# Motor_Control.net
KiCad netlist of a schematic drawn in Altium Designer
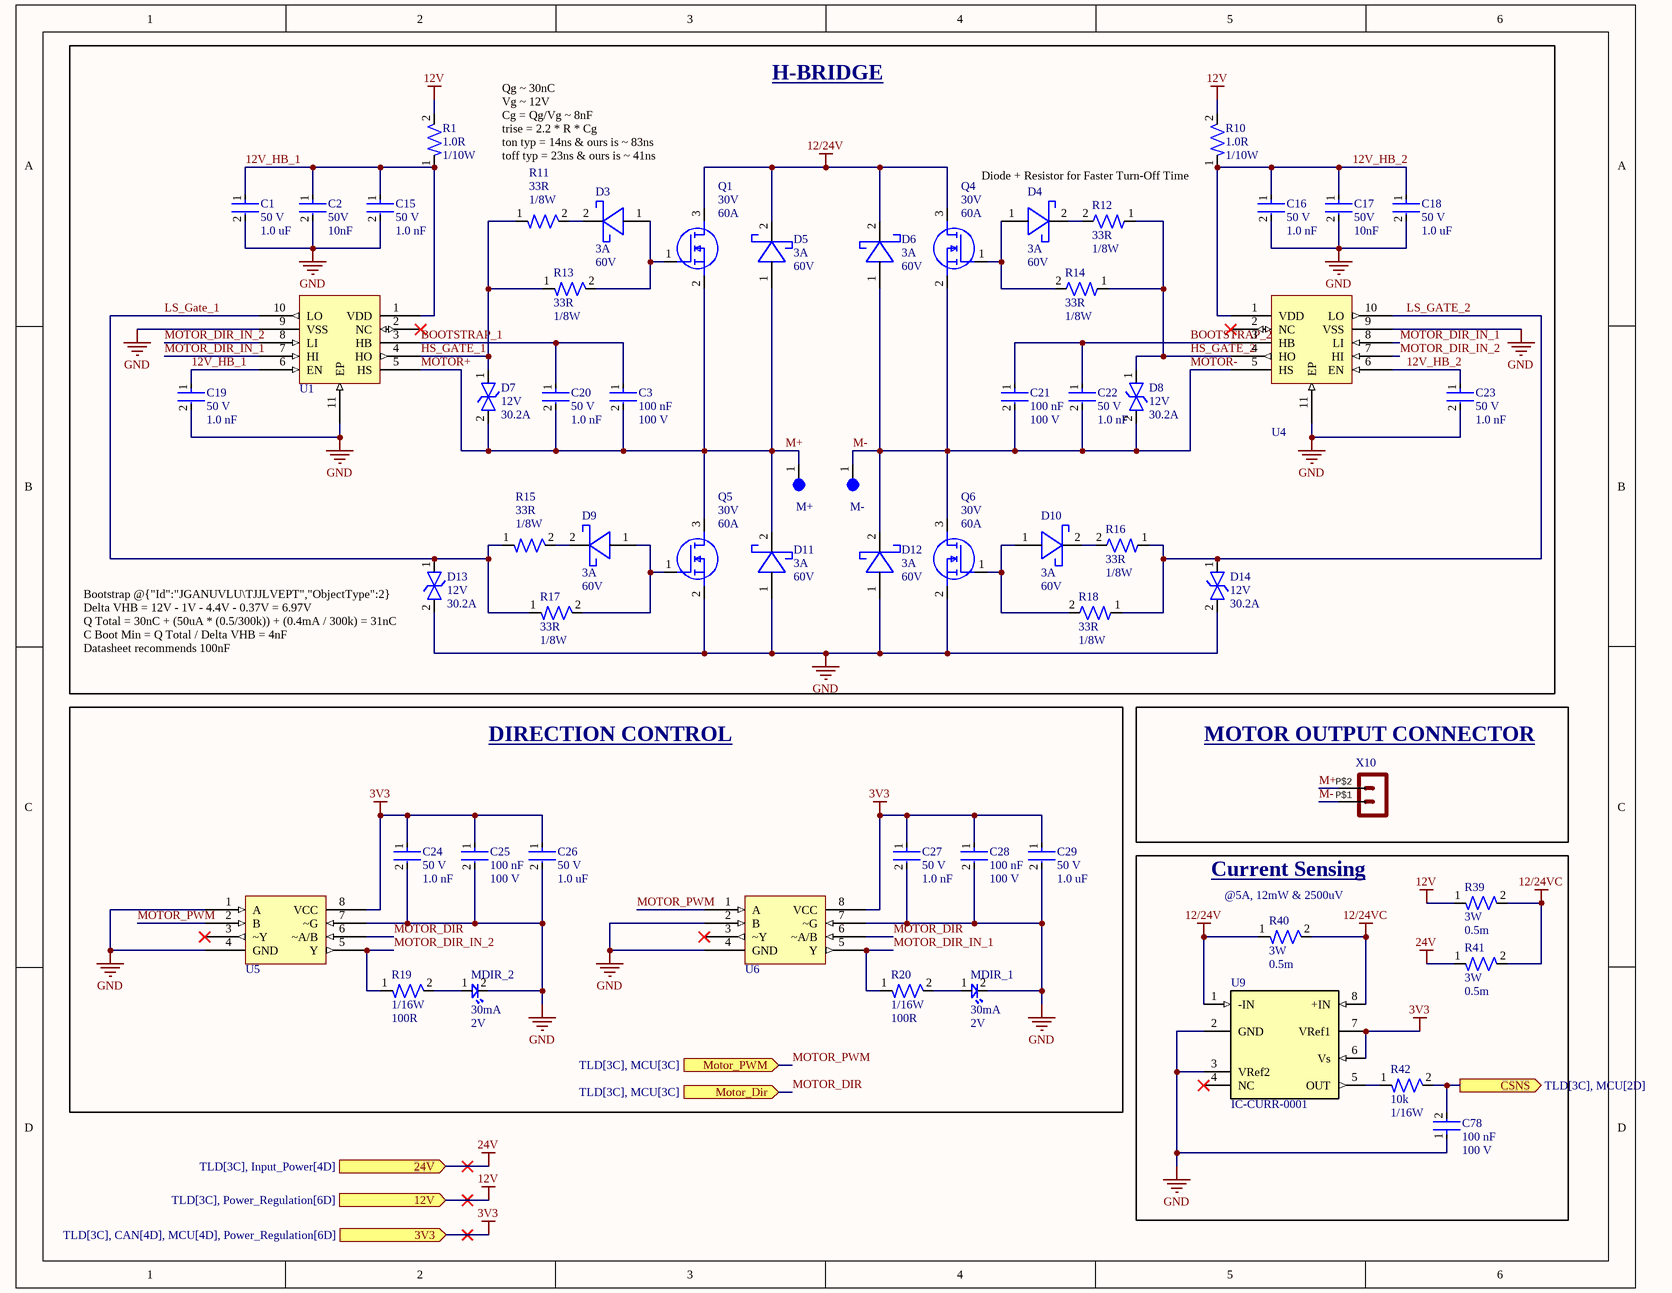
[diagram p0: Motor_Control.SchDoc]

(export (version "E")
  (design (tool "Eeschema 10.0.6"))
  (components
    (comp (ref "C1")
      (value "CC0805KKX7R9BB105")
      (footprint "CAP-0805")
      (description "CAP CER 1UF 50V X7R 0805")
      (fields (field (name "VOLTAGE") "50 V") (field (name "CAPACITANCE") "1.0 uF"))
      (libsource (lib "JLC_25") (part "CAP-1U-0001"))
    )
    (comp (ref "C2")
      (value "GRM2195C1H103JA01D")
      (footprint "CAP-0805")
      (description "CAP CER 10000PF 50V C0G/NP0 0805")
      (fields (field (name "VOLTAGE") "50V") (field (name "CAPACITANCE") "10nF"))
      (libsource (lib "JLC_25") (part "CAP-10N-0001"))
    )
    (comp (ref "C3")
      (value "CC0603KRX7R0BB104")
      (footprint "CAP-0603")
      (description "CAP CER 0.1UF 100V X7R 0603")
      (fields (field (name "CAPACITANCE") "100 nF") (field (name "VOLTAGE") "100 V"))
      (libsource (lib "JLC_25") (part "CAP-100N-0001"))
    )
    (comp (ref "C15")
      (value "CC0402KRX7R9BB102")
      (footprint "CAP-0402")
      (description "CAP CER 1000PF 50V X7R 0402")
      (fields (field (name "VOLTAGE") "50 V") (field (name "CAPACITANCE") "1.0 nF"))
      (libsource (lib "JLC_25") (part "CAP-1N-0001"))
    )
    (comp (ref "C16")
      (value "CC0402KRX7R9BB102")
      (footprint "CAP-0402")
      (description "CAP CER 1000PF 50V X7R 0402")
      (fields (field (name "VOLTAGE") "50 V") (field (name "CAPACITANCE") "1.0 nF"))
      (libsource (lib "JLC_25") (part "CAP-1N-0001"))
    )
    (comp (ref "C17")
      (value "GRM2195C1H103JA01D")
      (footprint "CAP-0805")
      (description "CAP CER 10000PF 50V C0G/NP0 0805")
      (fields (field (name "VOLTAGE") "50V") (field (name "CAPACITANCE") "10nF"))
      (libsource (lib "JLC_25") (part "CAP-10N-0001"))
    )
    (comp (ref "C18")
      (value "CC0805KKX7R9BB105")
      (footprint "CAP-0805")
      (description "CAP CER 1UF 50V X7R 0805")
      (fields (field (name "VOLTAGE") "50 V") (field (name "CAPACITANCE") "1.0 uF"))
      (libsource (lib "JLC_25") (part "CAP-1U-0001"))
    )
    (comp (ref "C19")
      (value "CC0402KRX7R9BB102")
      (footprint "CAP-0402")
      (description "CAP CER 1000PF 50V X7R 0402")
      (fields (field (name "VOLTAGE") "50 V") (field (name "CAPACITANCE") "1.0 nF"))
      (libsource (lib "JLC_25") (part "CAP-1N-0001"))
    )
    (comp (ref "C20")
      (value "CC0402KRX7R9BB102")
      (footprint "CAP-0402")
      (description "CAP CER 1000PF 50V X7R 0402")
      (fields (field (name "VOLTAGE") "50 V") (field (name "CAPACITANCE") "1.0 nF"))
      (libsource (lib "JLC_25") (part "CAP-1N-0001"))
    )
    (comp (ref "C21")
      (value "CC0603KRX7R0BB104")
      (footprint "CAP-0603")
      (description "CAP CER 0.1UF 100V X7R 0603")
      (fields (field (name "CAPACITANCE") "100 nF") (field (name "VOLTAGE") "100 V"))
      (libsource (lib "JLC_25") (part "CAP-100N-0001"))
    )
    (comp (ref "C22")
      (value "CC0402KRX7R9BB102")
      (footprint "CAP-0402")
      (description "CAP CER 1000PF 50V X7R 0402")
      (fields (field (name "VOLTAGE") "50 V") (field (name "CAPACITANCE") "1.0 nF"))
      (libsource (lib "JLC_25") (part "CAP-1N-0001"))
    )
    (comp (ref "C23")
      (value "CC0402KRX7R9BB102")
      (footprint "CAP-0402")
      (description "CAP CER 1000PF 50V X7R 0402")
      (fields (field (name "VOLTAGE") "50 V") (field (name "CAPACITANCE") "1.0 nF"))
      (libsource (lib "JLC_25") (part "CAP-1N-0001"))
    )
    (comp (ref "C24")
      (value "CC0402KRX7R9BB102")
      (footprint "CAP-0402")
      (description "CAP CER 1000PF 50V X7R 0402")
      (fields (field (name "VOLTAGE") "50 V") (field (name "CAPACITANCE") "1.0 nF"))
      (libsource (lib "JLC_25") (part "CAP-1N-0001"))
    )
    (comp (ref "C25")
      (value "CC0603KRX7R0BB104")
      (footprint "CAP-0603")
      (description "CAP CER 0.1UF 100V X7R 0603")
      (fields (field (name "CAPACITANCE") "100 nF") (field (name "VOLTAGE") "100 V"))
      (libsource (lib "JLC_25") (part "CAP-100N-0001"))
    )
    (comp (ref "C26")
      (value "CC0805KKX7R9BB105")
      (footprint "CAP-0805")
      (description "CAP CER 1UF 50V X7R 0805")
      (fields (field (name "VOLTAGE") "50 V") (field (name "CAPACITANCE") "1.0 uF"))
      (libsource (lib "JLC_25") (part "CAP-1U-0001"))
    )
    (comp (ref "C27")
      (value "CC0402KRX7R9BB102")
      (footprint "CAP-0402")
      (description "CAP CER 1000PF 50V X7R 0402")
      (fields (field (name "VOLTAGE") "50 V") (field (name "CAPACITANCE") "1.0 nF"))
      (libsource (lib "JLC_25") (part "CAP-1N-0001"))
    )
    (comp (ref "C28")
      (value "CC0603KRX7R0BB104")
      (footprint "CAP-0603")
      (description "CAP CER 0.1UF 100V X7R 0603")
      (fields (field (name "CAPACITANCE") "100 nF") (field (name "VOLTAGE") "100 V"))
      (libsource (lib "JLC_25") (part "CAP-100N-0001"))
    )
    (comp (ref "C29")
      (value "CC0805KKX7R9BB105")
      (footprint "CAP-0805")
      (description "CAP CER 1UF 50V X7R 0805")
      (fields (field (name "VOLTAGE") "50 V") (field (name "CAPACITANCE") "1.0 uF"))
      (libsource (lib "JLC_25") (part "CAP-1U-0001"))
    )
    (comp (ref "C78")
      (value "CC0603KRX7R0BB104")
      (footprint "CAP-0603")
      (description "CAP CER 0.1UF 100V X7R 0603")
      (fields (field (name "CAPACITANCE") "100 nF") (field (name "VOLTAGE") "100 V"))
      (libsource (lib "JLC_25") (part "CAP-100N-0001"))
    )
    (comp (ref "D3")
      (value "PMEG6030EP,115")
      (footprint "DIO-SOD128")
      (description "DIODE SCHOTTKY 60V 3A SOD128")
      (fields (field (name "CURRENT RATING") "3A") (field (name "REVERSE VOLTAGE") "60V"))
      (libsource (lib "JLC_25") (part "DIO-SCHOTTKY-0003"))
    )
    (comp (ref "D4")
      (value "PMEG6030EP,115")
      (footprint "DIO-SOD128")
      (description "DIODE SCHOTTKY 60V 3A SOD128")
      (fields (field (name "CURRENT RATING") "3A") (field (name "REVERSE VOLTAGE") "60V"))
      (libsource (lib "JLC_25") (part "DIO-SCHOTTKY-0003"))
    )
    (comp (ref "D5")
      (value "PMEG6030EP,115")
      (footprint "DIO-SOD128")
      (description "DIODE SCHOTTKY 60V 3A SOD128")
      (fields (field (name "CURRENT RATING") "3A") (field (name "REVERSE VOLTAGE") "60V"))
      (libsource (lib "JLC_25") (part "DIO-SCHOTTKY-0003"))
    )
    (comp (ref "D6")
      (value "PMEG6030EP,115")
      (footprint "DIO-SOD128")
      (description "DIODE SCHOTTKY 60V 3A SOD128")
      (fields (field (name "CURRENT RATING") "3A") (field (name "REVERSE VOLTAGE") "60V"))
      (libsource (lib "JLC_25") (part "DIO-SCHOTTKY-0003"))
    )
    (comp (ref "D7")
      (value "SMBJ12CA")
      (footprint "DO-214AA (SMBJ)")
      (description "TVS DIODE 12VWM 19.9VC DO214AA")
      (fields (field (name "STANDOFF VOLTAGE") "12V") (field (name "CURRENT RATING") "30.2A"))
      (libsource (lib "JLC_25") (part "DIO-TVS-0002"))
    )
    (comp (ref "D8")
      (value "SMBJ12CA")
      (footprint "DO-214AA (SMBJ)")
      (description "TVS DIODE 12VWM 19.9VC DO214AA")
      (fields (field (name "STANDOFF VOLTAGE") "12V") (field (name "CURRENT RATING") "30.2A"))
      (libsource (lib "JLC_25") (part "DIO-TVS-0002"))
    )
    (comp (ref "D9")
      (value "PMEG6030EP,115")
      (footprint "DIO-SOD128")
      (description "DIODE SCHOTTKY 60V 3A SOD128")
      (fields (field (name "CURRENT RATING") "3A") (field (name "REVERSE VOLTAGE") "60V"))
      (libsource (lib "JLC_25") (part "DIO-SCHOTTKY-0003"))
    )
    (comp (ref "D10")
      (value "PMEG6030EP,115")
      (footprint "DIO-SOD128")
      (description "DIODE SCHOTTKY 60V 3A SOD128")
      (fields (field (name "CURRENT RATING") "3A") (field (name "REVERSE VOLTAGE") "60V"))
      (libsource (lib "JLC_25") (part "DIO-SCHOTTKY-0003"))
    )
    (comp (ref "D11")
      (value "PMEG6030EP,115")
      (footprint "DIO-SOD128")
      (description "DIODE SCHOTTKY 60V 3A SOD128")
      (fields (field (name "CURRENT RATING") "3A") (field (name "REVERSE VOLTAGE") "60V"))
      (libsource (lib "JLC_25") (part "DIO-SCHOTTKY-0003"))
    )
    (comp (ref "D12")
      (value "PMEG6030EP,115")
      (footprint "DIO-SOD128")
      (description "DIODE SCHOTTKY 60V 3A SOD128")
      (fields (field (name "CURRENT RATING") "3A") (field (name "REVERSE VOLTAGE") "60V"))
      (libsource (lib "JLC_25") (part "DIO-SCHOTTKY-0003"))
    )
    (comp (ref "D13")
      (value "SMBJ12CA")
      (footprint "DO-214AA (SMBJ)")
      (description "TVS DIODE 12VWM 19.9VC DO214AA")
      (fields (field (name "STANDOFF VOLTAGE") "12V") (field (name "CURRENT RATING") "30.2A"))
      (libsource (lib "JLC_25") (part "DIO-TVS-0002"))
    )
    (comp (ref "D14")
      (value "SMBJ12CA")
      (footprint "DO-214AA (SMBJ)")
      (description "TVS DIODE 12VWM 19.9VC DO214AA")
      (fields (field (name "STANDOFF VOLTAGE") "12V") (field (name "CURRENT RATING") "30.2A"))
      (libsource (lib "JLC_25") (part "DIO-TVS-0002"))
    )
    (comp (ref "M+")
      (value "5003")
      (footprint "TEST-POINT-0001")
      (description "Oranange PC Test Point, Miniature Phoisphor Bronze Silver Plating Through Hole Mounting Type")
      (libsource (lib "JLC_25") (part "TEST-POINT-0001"))
    )
    (comp (ref "M-")
      (value "5003")
      (footprint "TEST-POINT-0001")
      (description "Oranange PC Test Point, Miniature Phoisphor Bronze Silver Plating Through Hole Mounting Type")
      (libsource (lib "JLC_25") (part "TEST-POINT-0001"))
    )
    (comp (ref "MDIR_1")
      (value "BL-HKC36G-AV-TRB")
      (footprint "LED-0603")
      (description "LED YELLOW CLEAR 0603 SMD")
      (fields (field (name "FORWARD CURRENT") "30mA") (field (name "FORWARD VOLTAGE") "2V"))
      (libsource (lib "JLC_25") (part "LED-0001"))
    )
    (comp (ref "MDIR_2")
      (value "BL-HKC36G-AV-TRB")
      (footprint "LED-0603")
      (description "LED YELLOW CLEAR 0603 SMD")
      (fields (field (name "FORWARD CURRENT") "30mA") (field (name "FORWARD VOLTAGE") "2V"))
      (libsource (lib "JLC_25") (part "LED-0001"))
    )
    (comp (ref "Q1")
      (value "CSD17575Q3")
      (footprint "IC-8VSONCLIP")
      (description "MOSFET N-CH 30V 60A 8VSON")
      (fields (field (name "VOLTAGE") "30V") (field (name "CONTINUOUS CURRENT") "60A"))
      (libsource (lib "JLC_25") (part "NMOS-26A-0001"))
    )
    (comp (ref "Q4")
      (value "CSD17575Q3")
      (footprint "IC-8VSONCLIP")
      (description "MOSFET N-CH 30V 60A 8VSON")
      (fields (field (name "VOLTAGE") "30V") (field (name "CONTINUOUS CURRENT") "60A"))
      (libsource (lib "JLC_25") (part "NMOS-26A-0001"))
    )
    (comp (ref "Q5")
      (value "CSD17575Q3")
      (footprint "IC-8VSONCLIP")
      (description "MOSFET N-CH 30V 60A 8VSON")
      (fields (field (name "VOLTAGE") "30V") (field (name "CONTINUOUS CURRENT") "60A"))
      (libsource (lib "JLC_25") (part "NMOS-26A-0001"))
    )
    (comp (ref "Q6")
      (value "CSD17575Q3")
      (footprint "IC-8VSONCLIP")
      (description "MOSFET N-CH 30V 60A 8VSON")
      (fields (field (name "VOLTAGE") "30V") (field (name "CONTINUOUS CURRENT") "60A"))
      (libsource (lib "JLC_25") (part "NMOS-26A-0001"))
    )
    (comp (ref "R1")
      (value "ERJ2GEJ1R0X")
      (footprint "RES-0402")
      (description "RES SMD 1 OHM 5% 1/10W 0402")
      (fields
        (field (name "TOLERANCE") "5%")
        (field (name "RESISTANCE") "1.0R")
        (field (name "POWER") "1/10W")
      )
      (libsource (lib "JLC_25") (part "RES-1-0001"))
    )
    (comp (ref "R10")
      (value "ERJ2GEJ1R0X")
      (footprint "RES-0402")
      (description "RES SMD 1 OHM 5% 1/10W 0402")
      (fields
        (field (name "TOLERANCE") "5%")
        (field (name "RESISTANCE") "1.0R")
        (field (name "POWER") "1/10W")
      )
      (libsource (lib "JLC_25") (part "RES-1-0001"))
    )
    (comp (ref "R11")
      (value "RC0402FR-7W33RL")
      (footprint "RES-0402")
      (description "RES 33 OHM 1% 1/8W 0402")
      (fields (field (name "TOLERANCE") "1%") (field (name "RESISTANCE") "33R") (field (name "POWER") "1/8W"))
      (libsource (lib "JLC_25") (part "RES-33-0001"))
    )
    (comp (ref "R12")
      (value "RC0402FR-7W33RL")
      (footprint "RES-0402")
      (description "RES 33 OHM 1% 1/8W 0402")
      (fields (field (name "TOLERANCE") "1%") (field (name "RESISTANCE") "33R") (field (name "POWER") "1/8W"))
      (libsource (lib "JLC_25") (part "RES-33-0001"))
    )
    (comp (ref "R13")
      (value "RC0402FR-7W33RL")
      (footprint "RES-0402")
      (description "RES 33 OHM 1% 1/8W 0402")
      (fields (field (name "TOLERANCE") "1%") (field (name "RESISTANCE") "33R") (field (name "POWER") "1/8W"))
      (libsource (lib "JLC_25") (part "RES-33-0001"))
    )
    (comp (ref "R14")
      (value "RC0402FR-7W33RL")
      (footprint "RES-0402")
      (description "RES 33 OHM 1% 1/8W 0402")
      (fields (field (name "TOLERANCE") "1%") (field (name "RESISTANCE") "33R") (field (name "POWER") "1/8W"))
      (libsource (lib "JLC_25") (part "RES-33-0001"))
    )
    (comp (ref "R15")
      (value "RC0402FR-7W33RL")
      (footprint "RES-0402")
      (description "RES 33 OHM 1% 1/8W 0402")
      (fields (field (name "TOLERANCE") "1%") (field (name "RESISTANCE") "33R") (field (name "POWER") "1/8W"))
      (libsource (lib "JLC_25") (part "RES-33-0001"))
    )
    (comp (ref "R16")
      (value "RC0402FR-7W33RL")
      (footprint "RES-0402")
      (description "RES 33 OHM 1% 1/8W 0402")
      (fields (field (name "TOLERANCE") "1%") (field (name "RESISTANCE") "33R") (field (name "POWER") "1/8W"))
      (libsource (lib "JLC_25") (part "RES-33-0001"))
    )
    (comp (ref "R17")
      (value "RC0402FR-7W33RL")
      (footprint "RES-0402")
      (description "RES 33 OHM 1% 1/8W 0402")
      (fields (field (name "TOLERANCE") "1%") (field (name "RESISTANCE") "33R") (field (name "POWER") "1/8W"))
      (libsource (lib "JLC_25") (part "RES-33-0001"))
    )
    (comp (ref "R18")
      (value "RC0402FR-7W33RL")
      (footprint "RES-0402")
      (description "RES 33 OHM 1% 1/8W 0402")
      (fields (field (name "TOLERANCE") "1%") (field (name "RESISTANCE") "33R") (field (name "POWER") "1/8W"))
      (libsource (lib "JLC_25") (part "RES-33-0001"))
    )
    (comp (ref "R19")
      (value "RC0402FR-07100RL")
      (footprint "RES-0402")
      (description "RES 100 OHM 1% 1/16W 0402")
      (fields
        (field (name "TOLERANCE") "1%")
        (field (name "POWER") "1/16W")
        (field (name "RESISTANCE") "100R")
      )
      (libsource (lib "JLC_25") (part "RES-100-0001"))
    )
    (comp (ref "R20")
      (value "RC0402FR-07100RL")
      (footprint "RES-0402")
      (description "RES 100 OHM 1% 1/16W 0402")
      (fields
        (field (name "TOLERANCE") "1%")
        (field (name "POWER") "1/16W")
        (field (name "RESISTANCE") "100R")
      )
      (libsource (lib "JLC_25") (part "RES-100-0001"))
    )
    (comp (ref "R39")
      (value "C337220")
      (footprint "RES-2512")
      (description "2512 Chip Resistor - Surface Mount ROHS")
      (fields (field (name "TOLERANCE") "1%") (field (name "POWER") "3W") (field (name "RESISTANCE") "0.5m"))
      (libsource (lib "JLC_25") (part "RES-0.5m-0001"))
    )
    (comp (ref "R40")
      (value "C337220")
      (footprint "RES-2512")
      (description "2512 Chip Resistor - Surface Mount ROHS")
      (fields (field (name "TOLERANCE") "1%") (field (name "POWER") "3W") (field (name "RESISTANCE") "0.5m"))
      (libsource (lib "JLC_25") (part "RES-0.5m-0001"))
    )
    (comp (ref "R41")
      (value "C337220")
      (footprint "RES-2512")
      (description "2512 Chip Resistor - Surface Mount ROHS")
      (fields (field (name "TOLERANCE") "1%") (field (name "POWER") "3W") (field (name "RESISTANCE") "0.5m"))
      (libsource (lib "JLC_25") (part "RES-0.5m-0001"))
    )
    (comp (ref "R42")
      (value "RC0402FR-0710KL")
      (footprint "RES-0402")
      (description "RES 10K OHM 1% 1/16W 0402")
      (fields
        (field (name "TOLERANCE") "1%")
        (field (name "RESISTANCE") "10k")
        (field (name "POWER") "1/16W")
      )
      (libsource (lib "JLC_25") (part "RES-10k-0001"))
    )
    (comp (ref "U1")
      (value "UCC27282DRCR")
      (footprint "IC-10VSON")
      (description "IC GATE DRVR HALF-BRIDGE 10VSON")
      (libsource (lib "") (part "IC-GTDR-0001_1"))
    )
    (comp (ref "U4")
      (value "UCC27282DRCR")
      (footprint "IC-10VSON")
      (description "IC GATE DRVR HALF-BRIDGE 10VSON")
      (libsource (lib "JLC_25") (part "IC-GTDR-0001"))
    )
    (comp (ref "U5")
      (value "SN74LVC2G157DCUR")
      (footprint "IC-8VSSOP")
      (description "Multiplexer 1 x 2:1 8-VSSOP")
      (libsource (lib "JLC_25") (part "IC-MUX-0001"))
    )
    (comp (ref "U6")
      (value "SN74LVC2G157DCUR")
      (footprint "IC-8VSSOP")
      (description "Multiplexer 1 x 2:1 8-VSSOP")
      (libsource (lib "JLC_25") (part "IC-MUX-0001"))
    )
    (comp (ref "U9")
      (value "IC-CURR-0001")
      (footprint "IC-CURR")
      (description "Current Sense Amplifier 1 Circuit 8-MSOP")
      (libsource (lib "JLC_25") (part "IC-CURR-0001"))
    )
    (comp (ref "X10")
      (value "Molex - Micro-Fit 3.0 Series connector,  3.00mm (0.118\") pitch header, 2 positions.")
      (footprint "43650-0200")
      (libsource (lib "Molex Microfit") (part "HEADER_POS2_?43650-0200"))
    )
  )
  (nets
    (net (code "1") (name "/12V_HB_1") (class "Default")
      (node (ref "C1") (pin "1") (pinfunction "1_1") (pintype "passive"))
      (node (ref "C15") (pin "1") (pinfunction "1_1") (pintype "passive"))
      (node (ref "C19") (pin "1") (pinfunction "1_1") (pintype "passive"))
      (node (ref "C2") (pin "1") (pinfunction "1_1") (pintype "passive"))
      (node (ref "R1") (pin "1") (pinfunction "1_1") (pintype "passive"))
      (node (ref "U1") (pin "1") (pinfunction "VDD_1") (pintype "power_in"))
      (node (ref "U1") (pin "6") (pinfunction "EN_6") (pintype "input"))
    )
    (net (code "2") (name "/12V_HB_2") (class "Default")
      (node (ref "C16") (pin "1") (pinfunction "1_1") (pintype "passive"))
      (node (ref "C17") (pin "1") (pinfunction "1_1") (pintype "passive"))
      (node (ref "C18") (pin "1") (pinfunction "1_1") (pintype "passive"))
      (node (ref "C23") (pin "1") (pinfunction "1_1") (pintype "passive"))
      (node (ref "R10") (pin "1") (pinfunction "1_1") (pintype "passive"))
      (node (ref "U4") (pin "1") (pinfunction "VDD_1") (pintype "power_in"))
      (node (ref "U4") (pin "6") (pinfunction "EN_6") (pintype "input"))
    )
    (net (code "3") (name "/BOOTSTRAP_1") (class "Default")
      (node (ref "C20") (pin "1") (pinfunction "1_1") (pintype "passive"))
      (node (ref "C3") (pin "1") (pinfunction "1_1") (pintype "passive"))
      (node (ref "U1") (pin "3") (pinfunction "HB_3") (pintype "power_in"))
    )
    (net (code "4") (name "/BOOTSTRAP_2") (class "Default")
      (node (ref "C21") (pin "1") (pinfunction "1_1") (pintype "passive"))
      (node (ref "C22") (pin "1") (pinfunction "1_1") (pintype "passive"))
      (node (ref "U4") (pin "3") (pinfunction "HB_3") (pintype "power_in"))
    )
    (net (code "5") (name "/CSNS") (class "Default")
      (node (ref "C78") (pin "2") (pinfunction "2_2") (pintype "passive"))
      (node (ref "R42") (pin "2") (pinfunction "2_2") (pintype "passive"))
    )
    (net (code "6") (name "/HS_GATE_1") (class "Default")
      (node (ref "D7") (pin "1") (pintype "passive"))
      (node (ref "R11") (pin "1") (pinfunction "1_1") (pintype "passive"))
      (node (ref "R13") (pin "1") (pinfunction "1_1") (pintype "passive"))
      (node (ref "U1") (pin "4") (pinfunction "HO_4") (pintype "output"))
    )
    (net (code "7") (name "/HS_GATE_2") (class "Default")
      (node (ref "D8") (pin "1") (pintype "passive"))
      (node (ref "R12") (pin "1") (pinfunction "1_1") (pintype "passive"))
      (node (ref "R14") (pin "1") (pinfunction "1_1") (pintype "passive"))
      (node (ref "U4") (pin "4") (pinfunction "HO_4") (pintype "output"))
    )
    (net (code "8") (name "/LS_GATE_2") (class "Default")
      (node (ref "D14") (pin "1") (pintype "passive"))
      (node (ref "R16") (pin "1") (pinfunction "1_1") (pintype "passive"))
      (node (ref "R18") (pin "1") (pinfunction "1_1") (pintype "passive"))
      (node (ref "U4") (pin "10") (pinfunction "LO_10") (pintype "output"))
    )
    (net (code "9") (name "/LS_Gate_1") (class "Default")
      (node (ref "D13") (pin "1") (pintype "passive"))
      (node (ref "R15") (pin "1") (pinfunction "1_1") (pintype "passive"))
      (node (ref "R17") (pin "1") (pinfunction "1_1") (pintype "passive"))
      (node (ref "U1") (pin "10") (pinfunction "LO_10") (pintype "output"))
    )
    (net (code "10") (name "/M+") (class "Default")
      (node (ref "C20") (pin "2") (pinfunction "2_2") (pintype "passive"))
      (node (ref "C3") (pin "2") (pinfunction "2_2") (pintype "passive"))
      (node (ref "D11") (pin "2") (pinfunction "ANODE_2") (pintype "passive"))
      (node (ref "D5") (pin "1") (pinfunction "CATHODE_1") (pintype "passive"))
      (node (ref "D7") (pin "2") (pintype "passive"))
      (node (ref "M+") (pin "1") (pinfunction "0_1") (pintype "passive"))
      (node (ref "Q1") (pin "2") (pinfunction "S_2") (pintype "passive"))
      (node (ref "Q5") (pin "3") (pinfunction "D_3") (pintype "passive"))
      (node (ref "U1") (pin "5") (pinfunction "HS_5") (pintype "power_in"))
      (node (ref "X10") (pin "P$2") (pinfunction "1_P$2") (pintype "passive"))
    )
    (net (code "11") (name "/M-") (class "Default")
      (node (ref "C21") (pin "2") (pinfunction "2_2") (pintype "passive"))
      (node (ref "C22") (pin "2") (pinfunction "2_2") (pintype "passive"))
      (node (ref "D12") (pin "2") (pinfunction "ANODE_2") (pintype "passive"))
      (node (ref "D6") (pin "1") (pinfunction "CATHODE_1") (pintype "passive"))
      (node (ref "D8") (pin "2") (pintype "passive"))
      (node (ref "M-") (pin "1") (pinfunction "0_1") (pintype "passive"))
      (node (ref "Q4") (pin "2") (pinfunction "S_2") (pintype "passive"))
      (node (ref "Q6") (pin "3") (pinfunction "D_3") (pintype "passive"))
      (node (ref "U4") (pin "5") (pinfunction "HS_5") (pintype "power_in"))
      (node (ref "X10") (pin "P$1") (pinfunction "2_P$1") (pintype "passive"))
    )
    (net (code "12") (name "/MOTOR_DIR") (class "Default")
      (node (ref "U5") (pin "6") (pinfunction "~A/B_6") (pintype "input"))
      (node (ref "U6") (pin "6") (pinfunction "~A/B_6") (pintype "input"))
    )
    (net (code "13") (name "/MOTOR_DIR_IN_1") (class "Default")
      (node (ref "R20") (pin "1") (pinfunction "1_1") (pintype "passive"))
      (node (ref "U1") (pin "7") (pinfunction "HI_7") (pintype "input"))
      (node (ref "U4") (pin "8") (pinfunction "LI_8") (pintype "input"))
      (node (ref "U6") (pin "5") (pinfunction "Y_5") (pintype "output"))
    )
    (net (code "14") (name "/MOTOR_DIR_IN_2") (class "Default")
      (node (ref "R19") (pin "1") (pinfunction "1_1") (pintype "passive"))
      (node (ref "U1") (pin "8") (pinfunction "LI_8") (pintype "input"))
      (node (ref "U4") (pin "7") (pinfunction "HI_7") (pintype "input"))
      (node (ref "U5") (pin "5") (pinfunction "Y_5") (pintype "output"))
    )
    (net (code "15") (name "/MOTOR_PWM") (class "Default")
      (node (ref "U5") (pin "2") (pinfunction "B_2") (pintype "input"))
      (node (ref "U6") (pin "1") (pinfunction "A_1") (pintype "input"))
    )
    (net (code "16") (name "3V3") (class "Default")
      (node (ref "C24") (pin "1") (pinfunction "1_1") (pintype "passive"))
      (node (ref "C25") (pin "1") (pinfunction "1_1") (pintype "passive"))
      (node (ref "C26") (pin "1") (pinfunction "1_1") (pintype "passive"))
      (node (ref "C27") (pin "1") (pinfunction "1_1") (pintype "passive"))
      (node (ref "C28") (pin "1") (pinfunction "1_1") (pintype "passive"))
      (node (ref "C29") (pin "1") (pinfunction "1_1") (pintype "passive"))
      (node (ref "U5") (pin "8") (pinfunction "VCC_8") (pintype "power_in"))
      (node (ref "U6") (pin "8") (pinfunction "VCC_8") (pintype "power_in"))
      (node (ref "U9") (pin "6") (pinfunction "Vs_6") (pintype "input"))
      (node (ref "U9") (pin "7") (pinfunction "VRef1_7") (pintype "power_in"))
    )
    (net (code "17") (name "12V") (class "Default")
      (node (ref "R1") (pin "2") (pinfunction "2_2") (pintype "passive"))
      (node (ref "R10") (pin "2") (pinfunction "2_2") (pintype "passive"))
      (node (ref "R39") (pin "1") (pinfunction "1_1") (pintype "passive"))
    )
    (net (code "18") (name "12{slash}24V") (class "Default")
      (node (ref "D5") (pin "2") (pinfunction "ANODE_2") (pintype "passive"))
      (node (ref "D6") (pin "2") (pinfunction "ANODE_2") (pintype "passive"))
      (node (ref "Q1") (pin "3") (pinfunction "D_3") (pintype "passive"))
      (node (ref "Q4") (pin "3") (pinfunction "D_3") (pintype "passive"))
      (node (ref "R40") (pin "1") (pinfunction "1_1") (pintype "passive"))
      (node (ref "U9") (pin "1") (pinfunction "-IN_1") (pintype "input"))
    )
    (net (code "19") (name "12{slash}24VC") (class "Default")
      (node (ref "R39") (pin "2") (pinfunction "2_2") (pintype "passive"))
      (node (ref "R40") (pin "2") (pinfunction "2_2") (pintype "passive"))
      (node (ref "R41") (pin "2") (pinfunction "2_2") (pintype "passive"))
      (node (ref "U9") (pin "8") (pinfunction "+IN_8") (pintype "input"))
    )
    (net (code "20") (name "24V") (class "Default")
      (node (ref "R41") (pin "1") (pinfunction "1_1") (pintype "passive"))
    )
    (net (code "21") (name "GND") (class "Default")
      (node (ref "C1") (pin "2") (pinfunction "2_2") (pintype "passive"))
      (node (ref "C15") (pin "2") (pinfunction "2_2") (pintype "passive"))
      (node (ref "C16") (pin "2") (pinfunction "2_2") (pintype "passive"))
      (node (ref "C17") (pin "2") (pinfunction "2_2") (pintype "passive"))
      (node (ref "C18") (pin "2") (pinfunction "2_2") (pintype "passive"))
      (node (ref "C19") (pin "2") (pinfunction "2_2") (pintype "passive"))
      (node (ref "C2") (pin "2") (pinfunction "2_2") (pintype "passive"))
      (node (ref "C23") (pin "2") (pinfunction "2_2") (pintype "passive"))
      (node (ref "C24") (pin "2") (pinfunction "2_2") (pintype "passive"))
      (node (ref "C25") (pin "2") (pinfunction "2_2") (pintype "passive"))
      (node (ref "C26") (pin "2") (pinfunction "2_2") (pintype "passive"))
      (node (ref "C27") (pin "2") (pinfunction "2_2") (pintype "passive"))
      (node (ref "C28") (pin "2") (pinfunction "2_2") (pintype "passive"))
      (node (ref "C29") (pin "2") (pinfunction "2_2") (pintype "passive"))
      (node (ref "C78") (pin "1") (pinfunction "1_1") (pintype "passive"))
      (node (ref "D11") (pin "1") (pinfunction "CATHODE_1") (pintype "passive"))
      (node (ref "D12") (pin "1") (pinfunction "CATHODE_1") (pintype "passive"))
      (node (ref "D13") (pin "2") (pintype "passive"))
      (node (ref "D14") (pin "2") (pintype "passive"))
      (node (ref "MDIR_1") (pin "2") (pinfunction "2_2") (pintype "passive"))
      (node (ref "MDIR_2") (pin "2") (pinfunction "2_2") (pintype "passive"))
      (node (ref "Q5") (pin "2") (pinfunction "S_2") (pintype "passive"))
      (node (ref "Q6") (pin "2") (pinfunction "S_2") (pintype "passive"))
      (node (ref "U1") (pin "11") (pinfunction "EP_11") (pintype "input"))
      (node (ref "U1") (pin "9") (pinfunction "VSS_9") (pintype "power_in"))
      (node (ref "U4") (pin "11") (pinfunction "EP_11") (pintype "input"))
      (node (ref "U4") (pin "9") (pinfunction "VSS_9") (pintype "power_in"))
      (node (ref "U5") (pin "1") (pinfunction "A_1") (pintype "input"))
      (node (ref "U5") (pin "4") (pinfunction "GND_4") (pintype "power_in"))
      (node (ref "U5") (pin "7") (pinfunction "~G_7") (pintype "input"))
      (node (ref "U6") (pin "2") (pinfunction "B_2") (pintype "input"))
      (node (ref "U6") (pin "4") (pinfunction "GND_4") (pintype "power_in"))
      (node (ref "U6") (pin "7") (pinfunction "~G_7") (pintype "input"))
      (node (ref "U9") (pin "2") (pinfunction "GND_2") (pintype "power_in"))
      (node (ref "U9") (pin "3") (pinfunction "VRef2_3") (pintype "passive"))
    )
    (net (code "22") (name "Net-(D3-ANODE)") (class "Default")
      (node (ref "D3") (pin "2") (pinfunction "ANODE_2") (pintype "passive"))
      (node (ref "R11") (pin "2") (pinfunction "2_2") (pintype "passive"))
    )
    (net (code "23") (name "Net-(D3-CATHODE)") (class "Default")
      (node (ref "D3") (pin "1") (pinfunction "CATHODE_1") (pintype "passive"))
      (node (ref "Q1") (pin "1") (pinfunction "G_1") (pintype "passive"))
      (node (ref "R13") (pin "2") (pinfunction "2_2") (pintype "passive"))
    )
    (net (code "24") (name "Net-(D4-ANODE)") (class "Default")
      (node (ref "D4") (pin "2") (pinfunction "ANODE_2") (pintype "passive"))
      (node (ref "R12") (pin "2") (pinfunction "2_2") (pintype "passive"))
    )
    (net (code "25") (name "Net-(D4-CATHODE)") (class "Default")
      (node (ref "D4") (pin "1") (pinfunction "CATHODE_1") (pintype "passive"))
      (node (ref "Q4") (pin "1") (pinfunction "G_1") (pintype "passive"))
      (node (ref "R14") (pin "2") (pinfunction "2_2") (pintype "passive"))
    )
    (net (code "26") (name "Net-(D9-ANODE)") (class "Default")
      (node (ref "D9") (pin "2") (pinfunction "ANODE_2") (pintype "passive"))
      (node (ref "R15") (pin "2") (pinfunction "2_2") (pintype "passive"))
    )
    (net (code "27") (name "Net-(D9-CATHODE)") (class "Default")
      (node (ref "D9") (pin "1") (pinfunction "CATHODE_1") (pintype "passive"))
      (node (ref "Q5") (pin "1") (pinfunction "G_1") (pintype "passive"))
      (node (ref "R17") (pin "2") (pinfunction "2_2") (pintype "passive"))
    )
    (net (code "28") (name "Net-(D10-ANODE)") (class "Default")
      (node (ref "D10") (pin "2") (pinfunction "ANODE_2") (pintype "passive"))
      (node (ref "R16") (pin "2") (pinfunction "2_2") (pintype "passive"))
    )
    (net (code "29") (name "Net-(D10-CATHODE)") (class "Default")
      (node (ref "D10") (pin "1") (pinfunction "CATHODE_1") (pintype "passive"))
      (node (ref "Q6") (pin "1") (pinfunction "G_1") (pintype "passive"))
      (node (ref "R18") (pin "2") (pinfunction "2_2") (pintype "passive"))
    )
    (net (code "30") (name "Net-(MDIR_1-Pad1)") (class "Default")
      (node (ref "MDIR_1") (pin "1") (pinfunction "1_1") (pintype "passive"))
      (node (ref "R20") (pin "2") (pinfunction "2_2") (pintype "passive"))
    )
    (net (code "31") (name "Net-(MDIR_2-Pad1)") (class "Default")
      (node (ref "MDIR_2") (pin "1") (pinfunction "1_1") (pintype "passive"))
      (node (ref "R19") (pin "2") (pinfunction "2_2") (pintype "passive"))
    )
    (net (code "32") (name "Net-(U9-OUT)") (class "Default")
      (node (ref "R42") (pin "1") (pinfunction "1_1") (pintype "passive"))
      (node (ref "U9") (pin "5") (pinfunction "OUT_5") (pintype "output"))
    )
    (net (code "33") (name "unconnected-(U1-NC-Pad2)") (class "Default")
      (node (ref "U1") (pin "2") (pinfunction "NC_2") (pintype "bidirectional+no_connect"))
    )
    (net (code "34") (name "unconnected-(U4-NC-Pad2)") (class "Default")
      (node (ref "U4") (pin "2") (pinfunction "NC_2") (pintype "bidirectional+no_connect"))
    )
    (net (code "35") (name "unconnected-(U5-~Y-Pad3)") (class "Default")
      (node (ref "U5") (pin "3") (pinfunction "~Y_3") (pintype "output+no_connect"))
    )
    (net (code "36") (name "unconnected-(U6-~Y-Pad3)") (class "Default")
      (node (ref "U6") (pin "3") (pinfunction "~Y_3") (pintype "output+no_connect"))
    )
    (net (code "37") (name "unconnected-(U9-NC-Pad4)") (class "Default")
      (node (ref "U9") (pin "4") (pinfunction "NC_4") (pintype "passive+no_connect"))
    )
  )
)
